# rega_bis.net
KiCad netlist of a schematic drawn in EAGLE
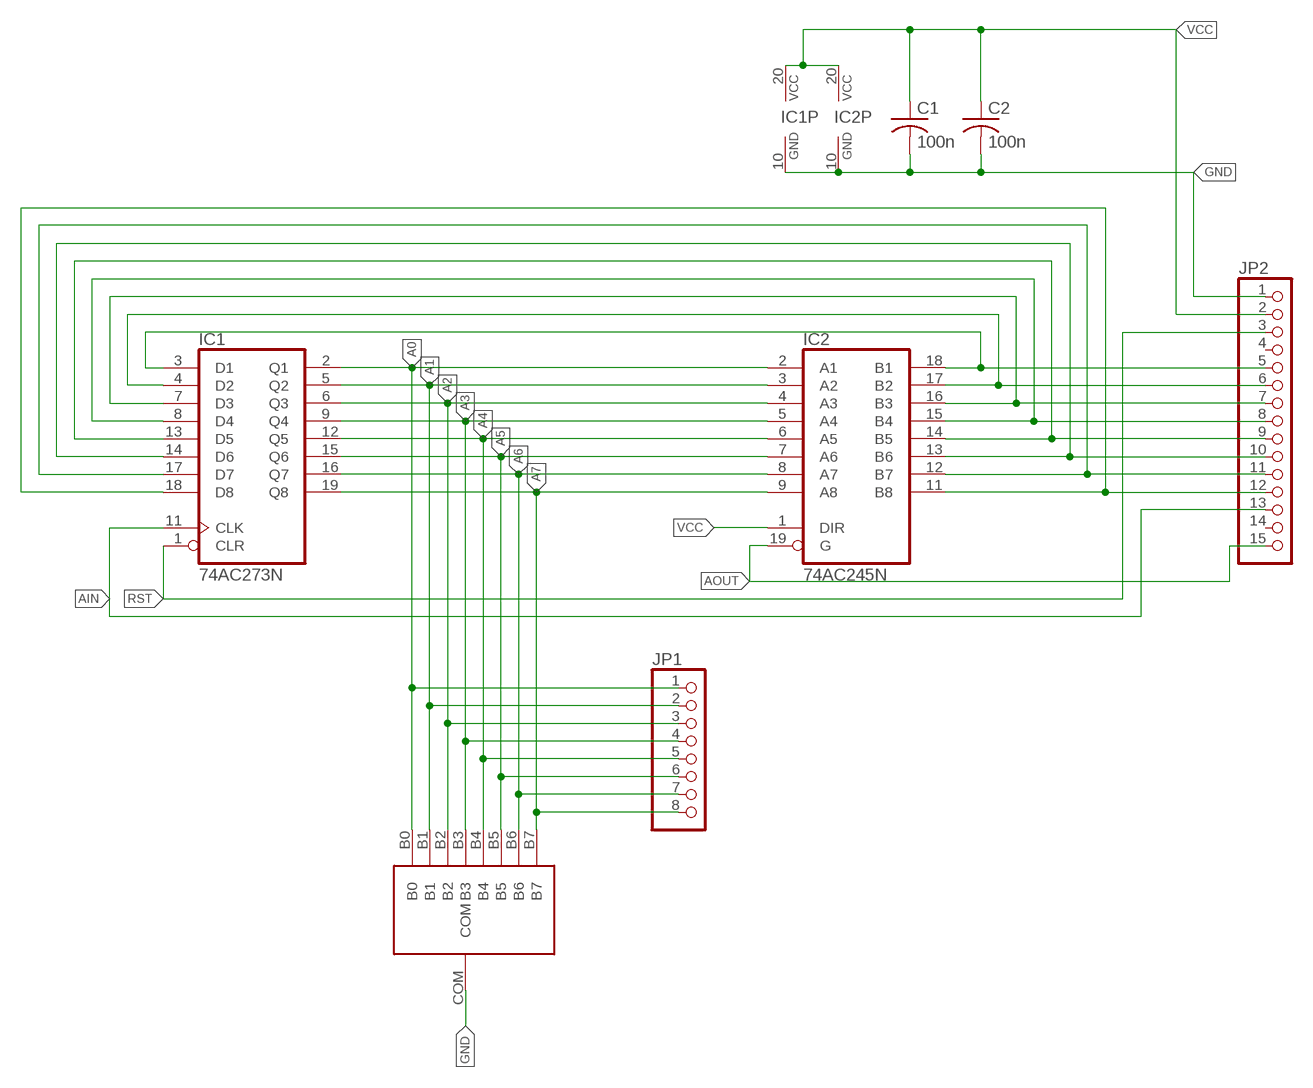
[diagram p0: schematic, sheet 1]

(export (version "E")
  (design (tool "Eeschema 10.0.6"))
  (components
    (comp (ref "C1")
      (value "100n")
      (footprint "eagle-import:C050-025X075")
      (libsource (lib "eagle-import") (part "C-US050-025X075"))
    )
    (comp (ref "C2")
      (value "100n")
      (footprint "eagle-import:C050-025X075")
      (libsource (lib "eagle-import") (part "C-US050-025X075"))
    )
    (comp (ref "IC1")
      (value "74AC273N")
      (footprint "eagle-import:DIL20")
      (libsource (lib "eagle-import") (part "74273NAC"))
    )
    (comp (ref "IC2")
      (value "74AC245N")
      (footprint "eagle-import:DIL20")
      (libsource (lib "eagle-import") (part "74245NAC"))
    )
    (comp (ref "JP1")
      (value "PINHD-1X8")
      (footprint "eagle-import:1X08")
      (libsource (lib "eagle-import") (part "PINHD-1X8"))
    )
    (comp (ref "JP2")
      (value "PINHD-1X15/90")
      (footprint "eagle-import:1X15_90")
      (libsource (lib "eagle-import") (part "PINHD-1X15/90"))
    )
    (comp (ref "U$1")
      (value "LEDEDGEGRAPH")
      (footprint "eagle-import:LEDEDGEGRAPH")
      (libsource (lib "eagle-import") (part "LEDEDGEGRAPH"))
    )
  )
  (nets
    (net (code "1") (name "A0") (class "Default")
      (node (ref "IC1") (pin "2") (pinfunction "Q1_2") (pintype "output"))
      (node (ref "IC2") (pin "2") (pinfunction "A1_2") (pintype "bidirectional"))
      (node (ref "JP1") (pin "1") (pinfunction "1_1") (pintype "passive"))
      (node (ref "U$1") (pin "B0") (pinfunction "B0_B0") (pintype "bidirectional"))
    )
    (net (code "2") (name "A1") (class "Default")
      (node (ref "IC1") (pin "5") (pinfunction "Q2_5") (pintype "output"))
      (node (ref "IC2") (pin "3") (pinfunction "A2_3") (pintype "bidirectional"))
      (node (ref "JP1") (pin "2") (pinfunction "2_2") (pintype "passive"))
      (node (ref "U$1") (pin "B1") (pinfunction "B1_B1") (pintype "bidirectional"))
    )
    (net (code "3") (name "A2") (class "Default")
      (node (ref "IC1") (pin "6") (pinfunction "Q3_6") (pintype "output"))
      (node (ref "IC2") (pin "4") (pinfunction "A3_4") (pintype "bidirectional"))
      (node (ref "JP1") (pin "3") (pinfunction "3_3") (pintype "passive"))
      (node (ref "U$1") (pin "B2") (pinfunction "B2_B2") (pintype "bidirectional"))
    )
    (net (code "4") (name "A3") (class "Default")
      (node (ref "IC1") (pin "9") (pinfunction "Q4_9") (pintype "output"))
      (node (ref "IC2") (pin "5") (pinfunction "A4_5") (pintype "bidirectional"))
      (node (ref "JP1") (pin "4") (pinfunction "4_4") (pintype "passive"))
      (node (ref "U$1") (pin "B3") (pinfunction "B3_B3") (pintype "bidirectional"))
    )
    (net (code "5") (name "A4") (class "Default")
      (node (ref "IC1") (pin "12") (pinfunction "Q5_12") (pintype "output"))
      (node (ref "IC2") (pin "6") (pinfunction "A5_6") (pintype "bidirectional"))
      (node (ref "JP1") (pin "5") (pinfunction "5_5") (pintype "passive"))
      (node (ref "U$1") (pin "B4") (pinfunction "B4_B4") (pintype "bidirectional"))
    )
    (net (code "6") (name "A5") (class "Default")
      (node (ref "IC1") (pin "15") (pinfunction "Q6_15") (pintype "output"))
      (node (ref "IC2") (pin "7") (pinfunction "A6_7") (pintype "bidirectional"))
      (node (ref "JP1") (pin "6") (pinfunction "6_6") (pintype "passive"))
      (node (ref "U$1") (pin "B5") (pinfunction "B5_B5") (pintype "bidirectional"))
    )
    (net (code "7") (name "A6") (class "Default")
      (node (ref "IC1") (pin "16") (pinfunction "Q7_16") (pintype "output"))
      (node (ref "IC2") (pin "8") (pinfunction "A7_8") (pintype "bidirectional"))
      (node (ref "JP1") (pin "7") (pinfunction "7_7") (pintype "passive"))
      (node (ref "U$1") (pin "B6") (pinfunction "B6_B6") (pintype "bidirectional"))
    )
    (net (code "8") (name "A7") (class "Default")
      (node (ref "IC1") (pin "19") (pinfunction "Q8_19") (pintype "output"))
      (node (ref "IC2") (pin "9") (pinfunction "A8_9") (pintype "bidirectional"))
      (node (ref "JP1") (pin "8") (pinfunction "8_8") (pintype "passive"))
      (node (ref "U$1") (pin "B7") (pinfunction "B7_B7") (pintype "bidirectional"))
    )
    (net (code "9") (name "AIN") (class "Default")
      (node (ref "IC1") (pin "11") (pinfunction "CLK_11") (pintype "input"))
      (node (ref "JP2") (pin "13") (pinfunction "13_13") (pintype "passive"))
    )
    (net (code "10") (name "AOUT") (class "Default")
      (node (ref "IC2") (pin "19") (pinfunction "G_19") (pintype "input"))
      (node (ref "JP2") (pin "15") (pinfunction "15_15") (pintype "passive"))
    )
    (net (code "11") (name "GND") (class "Default")
      (node (ref "C1") (pin "2") (pinfunction "2_2") (pintype "passive"))
      (node (ref "C2") (pin "2") (pinfunction "2_2") (pintype "passive"))
      (node (ref "IC1") (pin "10") (pinfunction "GND_10") (pintype "power_in"))
      (node (ref "IC2") (pin "10") (pinfunction "GND_10") (pintype "power_in"))
      (node (ref "JP2") (pin "1") (pinfunction "1_1") (pintype "passive"))
      (node (ref "U$1") (pin "COM") (pinfunction "COM_COM") (pintype "bidirectional"))
    )
    (net (code "12") (name "Net-(IC1A-D1)") (class "Default")
      (node (ref "IC1") (pin "3") (pinfunction "D1_3") (pintype "input"))
      (node (ref "IC2") (pin "18") (pinfunction "B1_18") (pintype "bidirectional"))
      (node (ref "JP2") (pin "5") (pinfunction "5_5") (pintype "passive"))
    )
    (net (code "13") (name "Net-(IC1A-D2)") (class "Default")
      (node (ref "IC1") (pin "4") (pinfunction "D2_4") (pintype "input"))
      (node (ref "IC2") (pin "17") (pinfunction "B2_17") (pintype "bidirectional"))
      (node (ref "JP2") (pin "6") (pinfunction "6_6") (pintype "passive"))
    )
    (net (code "14") (name "Net-(IC1A-D3)") (class "Default")
      (node (ref "IC1") (pin "7") (pinfunction "D3_7") (pintype "input"))
      (node (ref "IC2") (pin "16") (pinfunction "B3_16") (pintype "bidirectional"))
      (node (ref "JP2") (pin "7") (pinfunction "7_7") (pintype "passive"))
    )
    (net (code "15") (name "Net-(IC1A-D4)") (class "Default")
      (node (ref "IC1") (pin "8") (pinfunction "D4_8") (pintype "input"))
      (node (ref "IC2") (pin "15") (pinfunction "B4_15") (pintype "bidirectional"))
      (node (ref "JP2") (pin "8") (pinfunction "8_8") (pintype "passive"))
    )
    (net (code "16") (name "Net-(IC1A-D5)") (class "Default")
      (node (ref "IC1") (pin "13") (pinfunction "D5_13") (pintype "input"))
      (node (ref "IC2") (pin "14") (pinfunction "B5_14") (pintype "bidirectional"))
      (node (ref "JP2") (pin "9") (pinfunction "9_9") (pintype "passive"))
    )
    (net (code "17") (name "Net-(IC1A-D6)") (class "Default")
      (node (ref "IC1") (pin "14") (pinfunction "D6_14") (pintype "input"))
      (node (ref "IC2") (pin "13") (pinfunction "B6_13") (pintype "bidirectional"))
      (node (ref "JP2") (pin "10") (pinfunction "10_10") (pintype "passive"))
    )
    (net (code "18") (name "Net-(IC1A-D7)") (class "Default")
      (node (ref "IC1") (pin "17") (pinfunction "D7_17") (pintype "input"))
      (node (ref "IC2") (pin "12") (pinfunction "B7_12") (pintype "bidirectional"))
      (node (ref "JP2") (pin "11") (pinfunction "11_11") (pintype "passive"))
    )
    (net (code "19") (name "Net-(IC1A-D8)") (class "Default")
      (node (ref "IC1") (pin "18") (pinfunction "D8_18") (pintype "input"))
      (node (ref "IC2") (pin "11") (pinfunction "B8_11") (pintype "bidirectional"))
      (node (ref "JP2") (pin "12") (pinfunction "12_12") (pintype "passive"))
    )
    (net (code "20") (name "RST") (class "Default")
      (node (ref "IC1") (pin "1") (pinfunction "CLR_1") (pintype "input"))
      (node (ref "JP2") (pin "3") (pinfunction "3_3") (pintype "passive"))
    )
    (net (code "21") (name "VCC") (class "Default")
      (node (ref "C1") (pin "1") (pinfunction "1_1") (pintype "passive"))
      (node (ref "C2") (pin "1") (pinfunction "1_1") (pintype "passive"))
      (node (ref "IC1") (pin "20") (pinfunction "VCC_20") (pintype "power_in"))
      (node (ref "IC2") (pin "1") (pinfunction "DIR_1") (pintype "input"))
      (node (ref "IC2") (pin "20") (pinfunction "VCC_20") (pintype "power_in"))
      (node (ref "JP2") (pin "2") (pinfunction "2_2") (pintype "passive"))
    )
    (net (code "22") (name "unconnected-(JP2-Pad4)") (class "Default")
      (node (ref "JP2") (pin "4") (pinfunction "4_4") (pintype "passive"))
    )
    (net (code "23") (name "unconnected-(JP2-Pad14)") (class "Default")
      (node (ref "JP2") (pin "14") (pinfunction "14_14") (pintype "passive"))
    )
  )
)
